# PM12_N5V5.net
KiCad netlist of a schematic drawn in Altium Designer
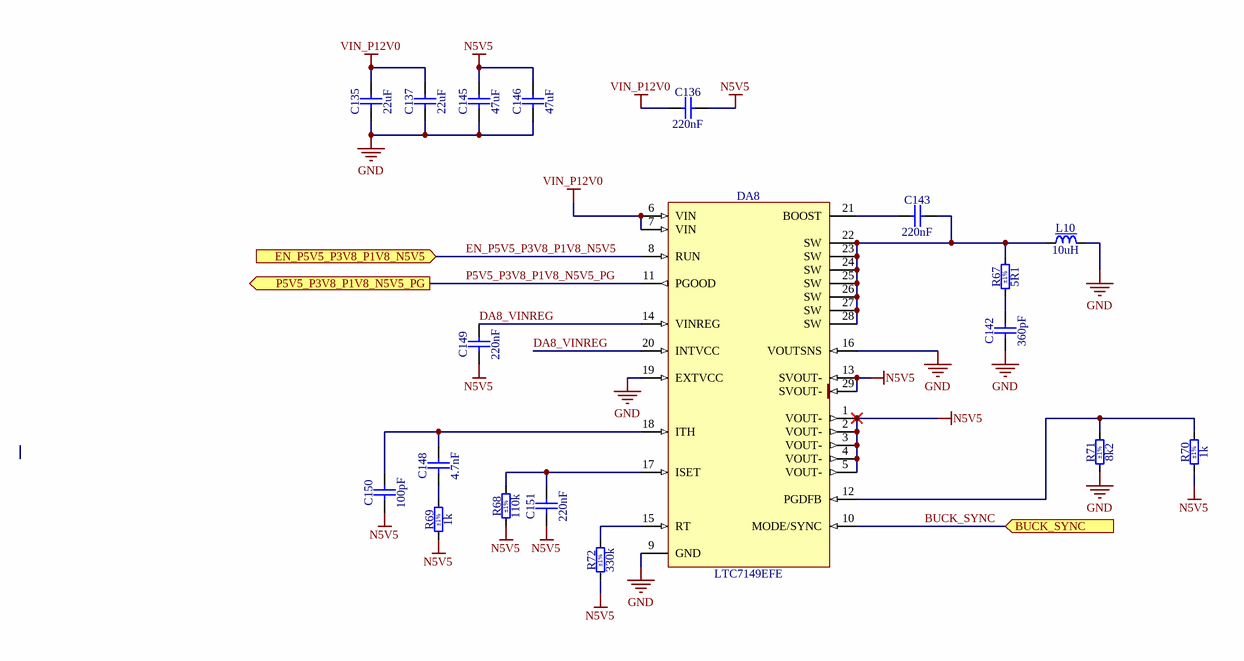
[diagram p0: PM12_N5V5.SchDoc]

(export (version "E")
  (design (tool "Eeschema 10.0.6"))
  (components
    (comp (ref "C135")
      (value "22uF")
      (footprint "CAPC3216X180N")
      (description "Non-polarised capacitor")
      (fields
        (field (name "PART NUMBER") "CC1206_22UF_25V_20%_X5R")
        (field (name "VOLTAGE") "25V")
        (field (name "AUTHOR") "CERN DEM WB")
      )
      (libsource (lib "Capacitors") (part "Capacitor - non polarized"))
    )
    (comp (ref "C136")
      (value "220nF")
      (footprint "CAPC2012X135N")
      (description "Non-polarised capacitor")
      (fields
        (field (name "PART NUMBER") "CC0805_220NF_50V_10%_X7R")
        (field (name "VOLTAGE") "50V")
        (field (name "AUTHOR") "CERN DEM JLC")
      )
      (libsource (lib "Capacitors") (part "Capacitor - non polarized"))
    )
    (comp (ref "C137")
      (value "22uF")
      (footprint "CAPC3216X180N")
      (description "Non-polarised capacitor")
      (fields
        (field (name "PART NUMBER") "CC1206_22UF_25V_20%_X5R")
        (field (name "VOLTAGE") "25V")
        (field (name "AUTHOR") "CERN DEM WB")
      )
      (libsource (lib "Capacitors") (part "Capacitor - non polarized"))
    )
    (comp (ref "C142")
      (value "360pF")
      (footprint "CAPC2013X145N")
      (description "Non-polarised capacitor")
      (fields
        (field (name "PART NUMBER") "CC0805_360PF_50V_5%_C0G")
        (field (name "VOLTAGE") "50V")
        (field (name "AUTHOR") "CERN DEM HF")
      )
      (libsource (lib "Capacitors") (part "Capacitor - non polarized"))
    )
    (comp (ref "C143")
      (value "220nF")
      (footprint "CAPC2012X135N")
      (description "Non-polarised capacitor")
      (fields
        (field (name "PART NUMBER") "CC0805_220NF_50V_10%_X7R")
        (field (name "VOLTAGE") "50V")
        (field (name "AUTHOR") "CERN DEM JLC")
      )
      (libsource (lib "Capacitors") (part "Capacitor - non polarized"))
    )
    (comp (ref "C145")
      (value "47uF")
      (footprint "CAPC3225X270N")
      (description "Non-polarised capacitor")
      (fields
        (field (name "PART NUMBER") "CC1210_47UF_16V_20%_X5R")
        (field (name "VOLTAGE") "16V")
        (field (name "AUTHOR") "CERN DEM MR")
      )
      (libsource (lib "Capacitors") (part "Capacitor - non polarized"))
    )
    (comp (ref "C146")
      (value "47uF")
      (footprint "CAPC3225X270N")
      (description "Non-polarised capacitor")
      (fields
        (field (name "PART NUMBER") "CC1210_47UF_16V_20%_X5R")
        (field (name "VOLTAGE") "16V")
        (field (name "AUTHOR") "CERN DEM MR")
      )
      (libsource (lib "Capacitors") (part "Capacitor - non polarized"))
    )
    (comp (ref "C148")
      (value "4.7nF")
      (footprint "CAPC2012X135N")
      (description "Non-polarised capacitor")
      (fields
        (field (name "PART NUMBER") "CC0805_4.7NF_50V_10%_X7R")
        (field (name "VOLTAGE") "50V")
        (field (name "AUTHOR") "CERN DEM JLC")
      )
      (libsource (lib "Capacitors") (part "Capacitor - non polarized"))
    )
    (comp (ref "C149")
      (value "220nF")
      (footprint "CAPC2012X135N")
      (description "Non-polarised capacitor")
      (fields
        (field (name "PART NUMBER") "CC0805_220NF_50V_10%_X7R")
        (field (name "VOLTAGE") "50V")
        (field (name "AUTHOR") "CERN DEM JLC")
      )
      (libsource (lib "Capacitors") (part "Capacitor - non polarized"))
    )
    (comp (ref "C150")
      (value "100pF")
      (footprint "CAPC2012X135N")
      (description "Non-polarised capacitor")
      (fields
        (field (name "PART NUMBER") "CC0805_100PF_50V_5%_NP0")
        (field (name "VOLTAGE") "50V")
        (field (name "AUTHOR") "CERN DEM JLC")
      )
      (libsource (lib "Capacitors") (part "Capacitor - non polarized"))
    )
    (comp (ref "C151")
      (value "220nF")
      (footprint "CAPC2012X135N")
      (description "Non-polarised capacitor")
      (fields
        (field (name "PART NUMBER") "CC0805_220NF_50V_10%_X7R")
        (field (name "VOLTAGE") "50V")
        (field (name "AUTHOR") "CERN DEM JLC")
      )
      (libsource (lib "Capacitors") (part "Capacitor - non polarized"))
    )
    (comp (ref "DA8")
      (value "LTC7149EFE")
      (footprint "SOP65P640X120-29N-R274X475")
      (description "60V, 4A Synchronous  Step-Down Regulator for Inverting Outputs")
      (fields (field (name "MANUFACTURER") "LINEAR TECHNOLOGY") (field (name "AUTHOR") "CERN DEM HF"))
      (libsource (lib "ICs And Semiconductors") (part "LTC7149XFE"))
    )
    (comp (ref "L10")
      (value "10uH")
      (footprint "IND_VISHAY_IHPL4040DZ-01")
      (description "Inductor With Core")
      (fields
        (field (name "PART NUMBER") "IND4040_10UH_20%_VISHAY_IHLP-4040DZ-01")
        (field (name "POWER") "6.8A")
        (field (name "AUTHOR") "CERN DEM HF")
      )
      (libsource (lib "Inductors & Transformers") (part "Inductor With Magnetic core"))
    )
    (comp (ref "R67")
      (value "5R1")
      (footprint "RESC2012X60N")
      (description "Resistor - 1%")
      (fields
        (field (name "TOLERANCE") "±1%")
        (field (name "PART NUMBER") "R0805_5R1_1%_0.125W_100PPM")
        (field (name "POWER") "0.125W")
        (field (name "AUTHOR") "CERN DEM HF")
      )
      (libsource (lib "Resistors") (part "Resistor - 1%"))
    )
    (comp (ref "R68")
      (value "110k")
      (footprint "RESC2012X60N")
      (description "Resistor - 1%")
      (fields
        (field (name "TOLERANCE") "±1%")
        (field (name "PART NUMBER") "R0805_110K_1%_0.125W_100PPM")
        (field (name "POWER") "0.125W")
        (field (name "AUTHOR") "CERN DEM JLC")
      )
      (libsource (lib "Resistors") (part "Resistor - 1%"))
    )
    (comp (ref "R69")
      (value "1k")
      (footprint "RESC1005X40N")
      (description "Resistor - 1%")
      (fields
        (field (name "TOLERANCE") "±1%")
        (field (name "PART NUMBER") "R0402_1K_1%_0.0625W_100PPM")
        (field (name "POWER") "0.0625W")
        (field (name "AUTHOR") "CERN DEM JLC")
      )
      (libsource (lib "Resistors") (part "Resistor - 1%"))
    )
    (comp (ref "R70")
      (value "1k")
      (footprint "RESC1005X40N")
      (description "Resistor - 1%")
      (fields
        (field (name "TOLERANCE") "±1%")
        (field (name "PART NUMBER") "R0402_1K_1%_0.0625W_100PPM")
        (field (name "POWER") "0.0625W")
        (field (name "AUTHOR") "CERN DEM JLC")
      )
      (libsource (lib "Resistors") (part "Resistor - 1%"))
    )
    (comp (ref "R71")
      (value "8k2")
      (footprint "RESC2012X60N")
      (description "Resistor - 1%")
      (fields
        (field (name "TOLERANCE") "±1%")
        (field (name "PART NUMBER") "R0805_8K2_1%_0.125W_100PPM")
        (field (name "POWER") "0.125W")
        (field (name "AUTHOR") "CERN DEM JLC")
      )
      (libsource (lib "Resistors") (part "Resistor - 1%"))
    )
    (comp (ref "R72")
      (value "330k")
      (footprint "RESC2012X60N")
      (description "Resistor - 1%")
      (fields
        (field (name "TOLERANCE") "±1%")
        (field (name "PART NUMBER") "R0805_330K_1%_0.125W_100PPM")
        (field (name "POWER") "0.125W")
        (field (name "AUTHOR") "CERN DEM JLC")
      )
      (libsource (lib "Resistors") (part "Resistor - 1%"))
    )
  )
  (nets
    (net (code "1") (name "/BUCK_SYNC") (class "Default")
      (node (ref "DA8") (pin "10") (pinfunction "MODE/SYNC_10") (pintype "input"))
    )
    (net (code "2") (name "/DA8_VINREG") (class "Default")
      (node (ref "C149") (pin "2") (pinfunction "2_2") (pintype "passive"))
      (node (ref "DA8") (pin "14") (pinfunction "VINREG_14") (pintype "input"))
      (node (ref "DA8") (pin "20") (pinfunction "INTVCC_20") (pintype "input"))
    )
    (net (code "3") (name "/EN_P5V5_P3V8_P1V8_N5V5") (class "Default")
      (node (ref "DA8") (pin "8") (pinfunction "RUN_8") (pintype "input"))
    )
    (net (code "4") (name "/P5V5_P3V8_P1V8_N5V5_PG") (class "Default")
      (node (ref "DA8") (pin "11") (pinfunction "PGOOD_11") (pintype "output"))
    )
    (net (code "5") (name "GND") (class "Default")
      (node (ref "C135") (pin "1") (pinfunction "1_1") (pintype "passive"))
      (node (ref "C137") (pin "1") (pinfunction "1_1") (pintype "passive"))
      (node (ref "C142") (pin "1") (pinfunction "1_1") (pintype "passive"))
      (node (ref "C145") (pin "1") (pinfunction "1_1") (pintype "passive"))
      (node (ref "C146") (pin "1") (pinfunction "1_1") (pintype "passive"))
      (node (ref "DA8") (pin "16") (pinfunction "VOUTSNS_16") (pintype "input"))
      (node (ref "DA8") (pin "19") (pinfunction "EXTVCC_19") (pintype "input"))
      (node (ref "DA8") (pin "9") (pinfunction "GND_9") (pintype "power_in"))
      (node (ref "L10") (pin "2") (pinfunction "2_2") (pintype "passive"))
      (node (ref "R71") (pin "1") (pinfunction "1_1") (pintype "passive"))
    )
    (net (code "6") (name "N5V5") (class "Default")
      (node (ref "C136") (pin "2") (pinfunction "2_2") (pintype "passive"))
      (node (ref "C145") (pin "2") (pinfunction "2_2") (pintype "passive"))
      (node (ref "C146") (pin "2") (pinfunction "2_2") (pintype "passive"))
      (node (ref "C149") (pin "1") (pinfunction "1_1") (pintype "passive"))
      (node (ref "C150") (pin "1") (pinfunction "1_1") (pintype "passive"))
      (node (ref "C151") (pin "1") (pinfunction "1_1") (pintype "passive"))
      (node (ref "DA8") (pin "1") (pinfunction "VOUT-_1") (pintype "output"))
      (node (ref "DA8") (pin "13") (pinfunction "SVOUT-_13") (pintype "input"))
      (node (ref "DA8") (pin "2") (pinfunction "VOUT-_2") (pintype "output"))
      (node (ref "DA8") (pin "29") (pinfunction "SVOUT-_29") (pintype "input"))
      (node (ref "DA8") (pin "3") (pinfunction "VOUT-_3") (pintype "output"))
      (node (ref "DA8") (pin "4") (pinfunction "VOUT-_4") (pintype "output"))
      (node (ref "DA8") (pin "5") (pinfunction "VOUT-_5") (pintype "output"))
      (node (ref "R68") (pin "1") (pinfunction "1_1") (pintype "passive"))
      (node (ref "R69") (pin "1") (pinfunction "1_1") (pintype "passive"))
      (node (ref "R70") (pin "1") (pinfunction "1_1") (pintype "passive"))
      (node (ref "R72") (pin "1") (pinfunction "1_1") (pintype "passive"))
    )
    (net (code "7") (name "Net-(C142-Pad2)") (class "Default")
      (node (ref "C142") (pin "2") (pinfunction "2_2") (pintype "passive"))
      (node (ref "R67") (pin "1") (pinfunction "1_1") (pintype "passive"))
    )
    (net (code "8") (name "Net-(C143-Pad2)") (class "Default")
      (node (ref "C143") (pin "2") (pinfunction "2_2") (pintype "passive"))
      (node (ref "DA8") (pin "22") (pinfunction "SW_22") (pintype "power_in"))
      (node (ref "DA8") (pin "23") (pinfunction "SW_23") (pintype "power_in"))
      (node (ref "DA8") (pin "24") (pinfunction "SW_24") (pintype "power_in"))
      (node (ref "DA8") (pin "25") (pinfunction "SW_25") (pintype "power_in"))
      (node (ref "DA8") (pin "26") (pinfunction "SW_26") (pintype "power_in"))
      (node (ref "DA8") (pin "27") (pinfunction "SW_27") (pintype "power_in"))
      (node (ref "DA8") (pin "28") (pinfunction "SW_28") (pintype "power_in"))
      (node (ref "L10") (pin "1") (pinfunction "1_1") (pintype "passive"))
      (node (ref "R67") (pin "2") (pinfunction "2_2") (pintype "passive"))
    )
    (net (code "9") (name "Net-(C148-Pad1)") (class "Default")
      (node (ref "C148") (pin "1") (pinfunction "1_1") (pintype "passive"))
      (node (ref "R69") (pin "2") (pinfunction "2_2") (pintype "passive"))
    )
    (net (code "10") (name "Net-(DA8-BOOST)") (class "Default")
      (node (ref "C143") (pin "1") (pinfunction "1_1") (pintype "passive"))
      (node (ref "DA8") (pin "21") (pinfunction "BOOST_21") (pintype "passive"))
    )
    (net (code "11") (name "Net-(DA8-ISET)") (class "Default")
      (node (ref "C151") (pin "2") (pinfunction "2_2") (pintype "passive"))
      (node (ref "DA8") (pin "17") (pinfunction "ISET_17") (pintype "input"))
      (node (ref "R68") (pin "2") (pinfunction "2_2") (pintype "passive"))
    )
    (net (code "12") (name "Net-(DA8-ITH)") (class "Default")
      (node (ref "C148") (pin "2") (pinfunction "2_2") (pintype "passive"))
      (node (ref "C150") (pin "2") (pinfunction "2_2") (pintype "passive"))
      (node (ref "DA8") (pin "18") (pinfunction "ITH_18") (pintype "input"))
    )
    (net (code "13") (name "Net-(DA8-PGDFB)") (class "Default")
      (node (ref "DA8") (pin "12") (pinfunction "PGDFB_12") (pintype "input"))
      (node (ref "R70") (pin "2") (pinfunction "2_2") (pintype "passive"))
      (node (ref "R71") (pin "2") (pinfunction "2_2") (pintype "passive"))
    )
    (net (code "14") (name "Net-(DA8-RT)") (class "Default")
      (node (ref "DA8") (pin "15") (pinfunction "RT_15") (pintype "input"))
      (node (ref "R72") (pin "2") (pinfunction "2_2") (pintype "passive"))
    )
    (net (code "15") (name "VIN_P12V0") (class "Default")
      (node (ref "C135") (pin "2") (pinfunction "2_2") (pintype "passive"))
      (node (ref "C136") (pin "1") (pinfunction "1_1") (pintype "passive"))
      (node (ref "C137") (pin "2") (pinfunction "2_2") (pintype "passive"))
      (node (ref "DA8") (pin "6") (pinfunction "VIN_6") (pintype "input"))
      (node (ref "DA8") (pin "7") (pinfunction "VIN_7") (pintype "input"))
    )
  )
)
